# boot_rig_esp.net
KiCad netlist of a schematic drawn in EAGLE
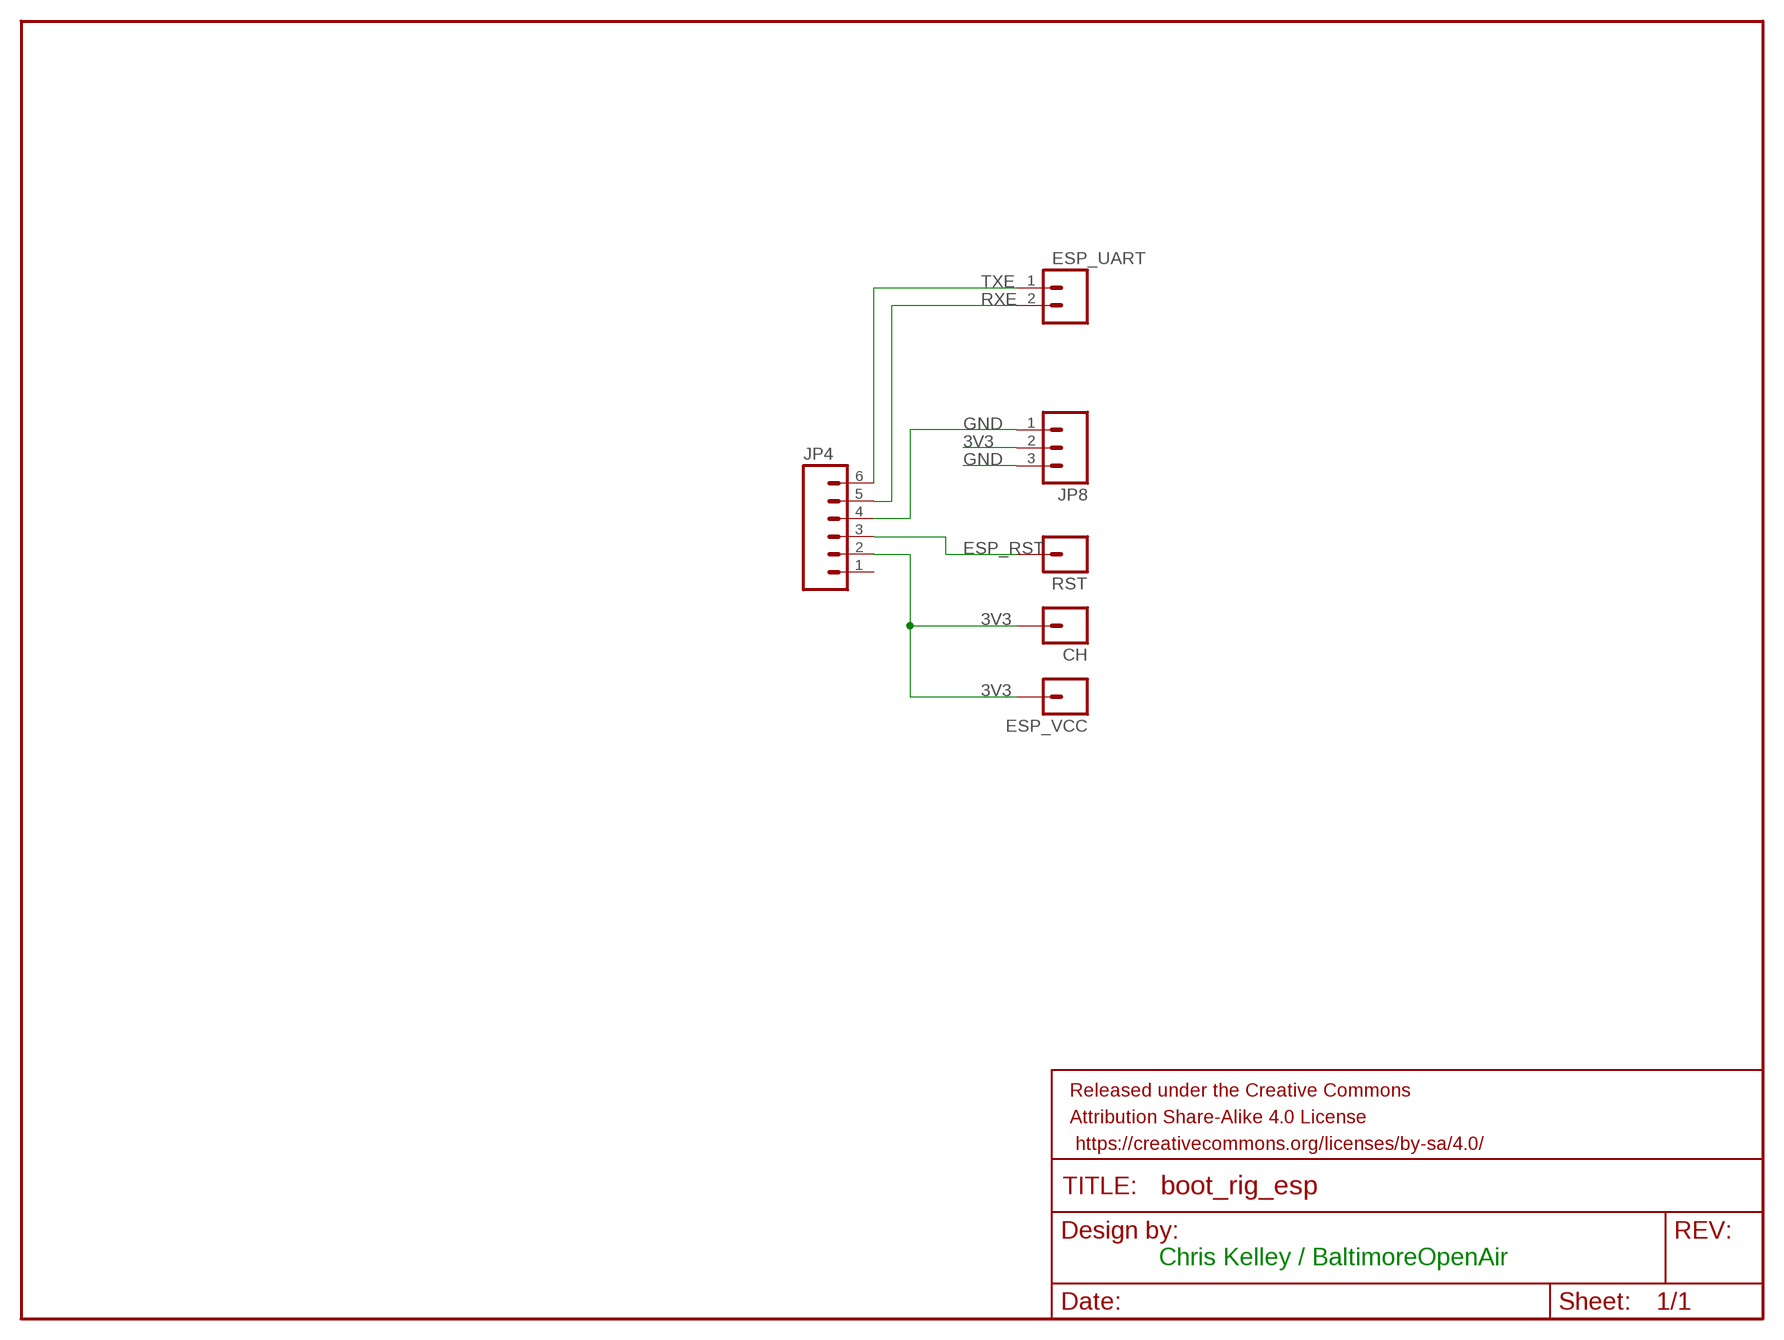
[diagram p0: schematic, sheet 1]

(export (version "E")
  (design (tool "Eeschema 10.0.6"))
  (components
    (comp (ref "CH")
      (value "M01PTH")
      (footprint "eagle-import:1X01")
      (libsource (lib "eagle-import") (part "M01PTH"))
    )
    (comp (ref "ESP_UART")
      (value "M02PTH")
      (footprint "eagle-import:1X02")
      (libsource (lib "eagle-import") (part "M02PTH"))
    )
    (comp (ref "ESP_VCC")
      (value "M01PTH")
      (footprint "eagle-import:1X01")
      (libsource (lib "eagle-import") (part "M01PTH"))
    )
    (comp (ref "FRAME1")
      (value "FRAME-LETTER")
      (footprint "eagle-import:CREATIVE_COMMONS")
      (libsource (lib "eagle-import") (part "FRAME-LETTER"))
    )
    (comp (ref "JP4")
      (value "M06SILK_FEMALE_PTH")
      (footprint "eagle-import:1X06")
      (libsource (lib "eagle-import") (part "M06SILK_FEMALE_PTH"))
    )
    (comp (ref "JP8")
      (value "M03PTH")
      (footprint "eagle-import:1X03")
      (libsource (lib "eagle-import") (part "M03PTH"))
    )
    (comp (ref "RST")
      (value "M01PTH")
      (footprint "eagle-import:1X01")
      (libsource (lib "eagle-import") (part "M01PTH"))
    )
  )
  (nets
    (net (code "1") (name "/3V3") (class "Default")
      (node (ref "CH") (pin "1") (pinfunction "1_1") (pintype "passive"))
      (node (ref "ESP_VCC") (pin "1") (pinfunction "1_1") (pintype "passive"))
      (node (ref "JP4") (pin "2") (pinfunction "2_2") (pintype "passive"))
      (node (ref "JP8") (pin "2") (pinfunction "2_2") (pintype "passive"))
    )
    (net (code "2") (name "/ESP_RST") (class "Default")
      (node (ref "JP4") (pin "3") (pinfunction "3_3") (pintype "passive"))
      (node (ref "RST") (pin "1") (pinfunction "1_1") (pintype "passive"))
    )
    (net (code "3") (name "/GND") (class "Default")
      (node (ref "JP4") (pin "4") (pinfunction "4_4") (pintype "passive"))
      (node (ref "JP8") (pin "1") (pinfunction "1_1") (pintype "passive"))
      (node (ref "JP8") (pin "3") (pinfunction "3_3") (pintype "passive"))
    )
    (net (code "4") (name "/RXE") (class "Default")
      (node (ref "ESP_UART") (pin "2") (pinfunction "2_2") (pintype "passive"))
      (node (ref "JP4") (pin "5") (pinfunction "5_5") (pintype "passive"))
    )
    (net (code "5") (name "/TXE") (class "Default")
      (node (ref "ESP_UART") (pin "1") (pinfunction "1_1") (pintype "passive"))
      (node (ref "JP4") (pin "6") (pinfunction "6_6") (pintype "passive"))
    )
    (net (code "6") (name "unconnected-(JP4-Pad1)") (class "Default")
      (node (ref "JP4") (pin "1") (pinfunction "1_1") (pintype "passive"))
    )
  )
)
